# USB.net
KiCad netlist of a schematic drawn in Altium Designer
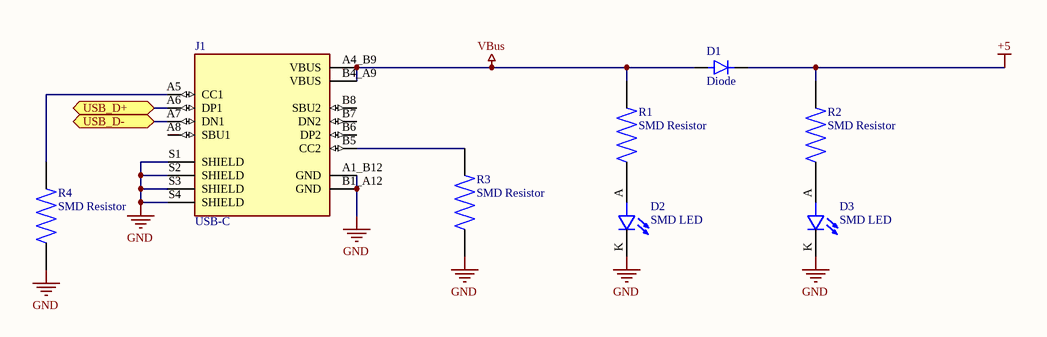
[diagram p0: USB.SchDoc]

(export (version "E")
  (design (tool "Eeschema 10.0.6"))
  (components
    (comp (ref "D1")
      (value "Diode")
      (footprint "Diode-Footprint-1")
      (description "Generic Diode")
      (libsource (lib "Tobias") (part "Diode-Symbol-1"))
    )
    (comp (ref "D2")
      (value "SMD LED")
      (footprint "SMD LED-Footprint-1")
      (description "Generic SMD LED")
      (libsource (lib "Tobias") (part "SMD LED-Symbol-1"))
    )
    (comp (ref "D3")
      (value "SMD LED")
      (footprint "SMD LED-Footprint-1")
      (description "Generic SMD LED")
      (libsource (lib "Tobias") (part "SMD LED-Symbol-1"))
    )
    (comp (ref "J1")
      (value "USB-C")
      (footprint "USB-C-Footprint-1")
      (description "USB-C Connector")
      (libsource (lib "Tobias") (part "USB-C-Symbol-1"))
    )
    (comp (ref "R1")
      (value "SMD Resistor")
      (footprint "SMD Resistor-Footprint-1")
      (description "Generic SMD Resistor")
      (libsource (lib "Tobias") (part "SMD Resistor-Symbol-1"))
    )
    (comp (ref "R2")
      (value "SMD Resistor")
      (footprint "SMD Resistor-Footprint-1")
      (description "Generic SMD Resistor")
      (libsource (lib "Tobias") (part "SMD Resistor-Symbol-1"))
    )
    (comp (ref "R3")
      (value "SMD Resistor")
      (footprint "SMD Resistor-Footprint-1")
      (description "Generic SMD Resistor")
      (libsource (lib "Tobias") (part "SMD Resistor-Symbol-1"))
    )
    (comp (ref "R4")
      (value "SMD Resistor")
      (footprint "SMD Resistor-Footprint-1")
      (description "Generic SMD Resistor")
      (libsource (lib "Tobias") (part "SMD Resistor-Symbol-1"))
    )
  )
  (nets
    (net (code "1") (name "+5") (class "Default")
      (node (ref "D1") (pin "K") (pinfunction "K_K") (pintype "passive"))
      (node (ref "R2") (pin "1") (pinfunction "1_1") (pintype "passive"))
    )
    (net (code "2") (name "/USB_D+") (class "Default")
      (node (ref "J1") (pin "A6") (pinfunction "DP1_A6") (pintype "bidirectional"))
    )
    (net (code "3") (name "/USB_D-") (class "Default")
      (node (ref "J1") (pin "A7") (pinfunction "DN1_A7") (pintype "bidirectional"))
    )
    (net (code "4") (name "GND") (class "Default")
      (node (ref "D2") (pin "K") (pinfunction "C_K") (pintype "passive"))
      (node (ref "D3") (pin "K") (pinfunction "C_K") (pintype "passive"))
      (node (ref "J1") (pin "A1_B12") (pinfunction "GND_A1_B12") (pintype "power_in"))
      (node (ref "J1") (pin "B1_A12") (pinfunction "GND_B1_A12") (pintype "power_in"))
      (node (ref "J1") (pin "S1") (pinfunction "SHIELD_S1") (pintype "passive"))
      (node (ref "J1") (pin "S2") (pinfunction "SHIELD_S2") (pintype "passive"))
      (node (ref "J1") (pin "S3") (pinfunction "SHIELD_S3") (pintype "passive"))
      (node (ref "J1") (pin "S4") (pinfunction "SHIELD_S4") (pintype "passive"))
      (node (ref "R3") (pin "2") (pinfunction "2_2") (pintype "passive"))
      (node (ref "R4") (pin "2") (pinfunction "2_2") (pintype "passive"))
    )
    (net (code "5") (name "Net-(D2-PadA)") (class "Default")
      (node (ref "D2") (pin "A") (pinfunction "A_A") (pintype "passive"))
      (node (ref "R1") (pin "2") (pinfunction "2_2") (pintype "passive"))
    )
    (net (code "6") (name "Net-(D3-PadA)") (class "Default")
      (node (ref "D3") (pin "A") (pinfunction "A_A") (pintype "passive"))
      (node (ref "R2") (pin "2") (pinfunction "2_2") (pintype "passive"))
    )
    (net (code "7") (name "Net-(J1-CC1)") (class "Default")
      (node (ref "J1") (pin "A5") (pinfunction "CC1_A5") (pintype "bidirectional"))
      (node (ref "R4") (pin "1") (pinfunction "1_1") (pintype "passive"))
    )
    (net (code "8") (name "Net-(J1-CC2)") (class "Default")
      (node (ref "J1") (pin "B5") (pinfunction "CC2_B5") (pintype "bidirectional"))
      (node (ref "R3") (pin "1") (pinfunction "1_1") (pintype "passive"))
    )
    (net (code "9") (name "VBus") (class "Default")
      (node (ref "D1") (pin "A") (pinfunction "A_A") (pintype "passive"))
      (node (ref "J1") (pin "A4_B9") (pinfunction "VBUS_A4_B9") (pintype "power_in"))
      (node (ref "J1") (pin "B4_A9") (pinfunction "VBUS_B4_A9") (pintype "power_in"))
      (node (ref "R1") (pin "1") (pinfunction "1_1") (pintype "passive"))
    )
    (net (code "10") (name "unconnected-(J1-DN2-PadB7)") (class "Default")
      (node (ref "J1") (pin "B7") (pinfunction "DN2_B7") (pintype "bidirectional"))
    )
    (net (code "11") (name "unconnected-(J1-DP2-PadB6)") (class "Default")
      (node (ref "J1") (pin "B6") (pinfunction "DP2_B6") (pintype "bidirectional"))
    )
    (net (code "12") (name "unconnected-(J1-SBU1-PadA8)") (class "Default")
      (node (ref "J1") (pin "A8") (pinfunction "SBU1_A8") (pintype "bidirectional"))
    )
    (net (code "13") (name "unconnected-(J1-SBU2-PadB8)") (class "Default")
      (node (ref "J1") (pin "B8") (pinfunction "SBU2_B8") (pintype "bidirectional"))
    )
  )
)
